# IMU_Raspberry_Pi_Breakout_RevB.net
KiCad netlist of a schematic drawn in EAGLE
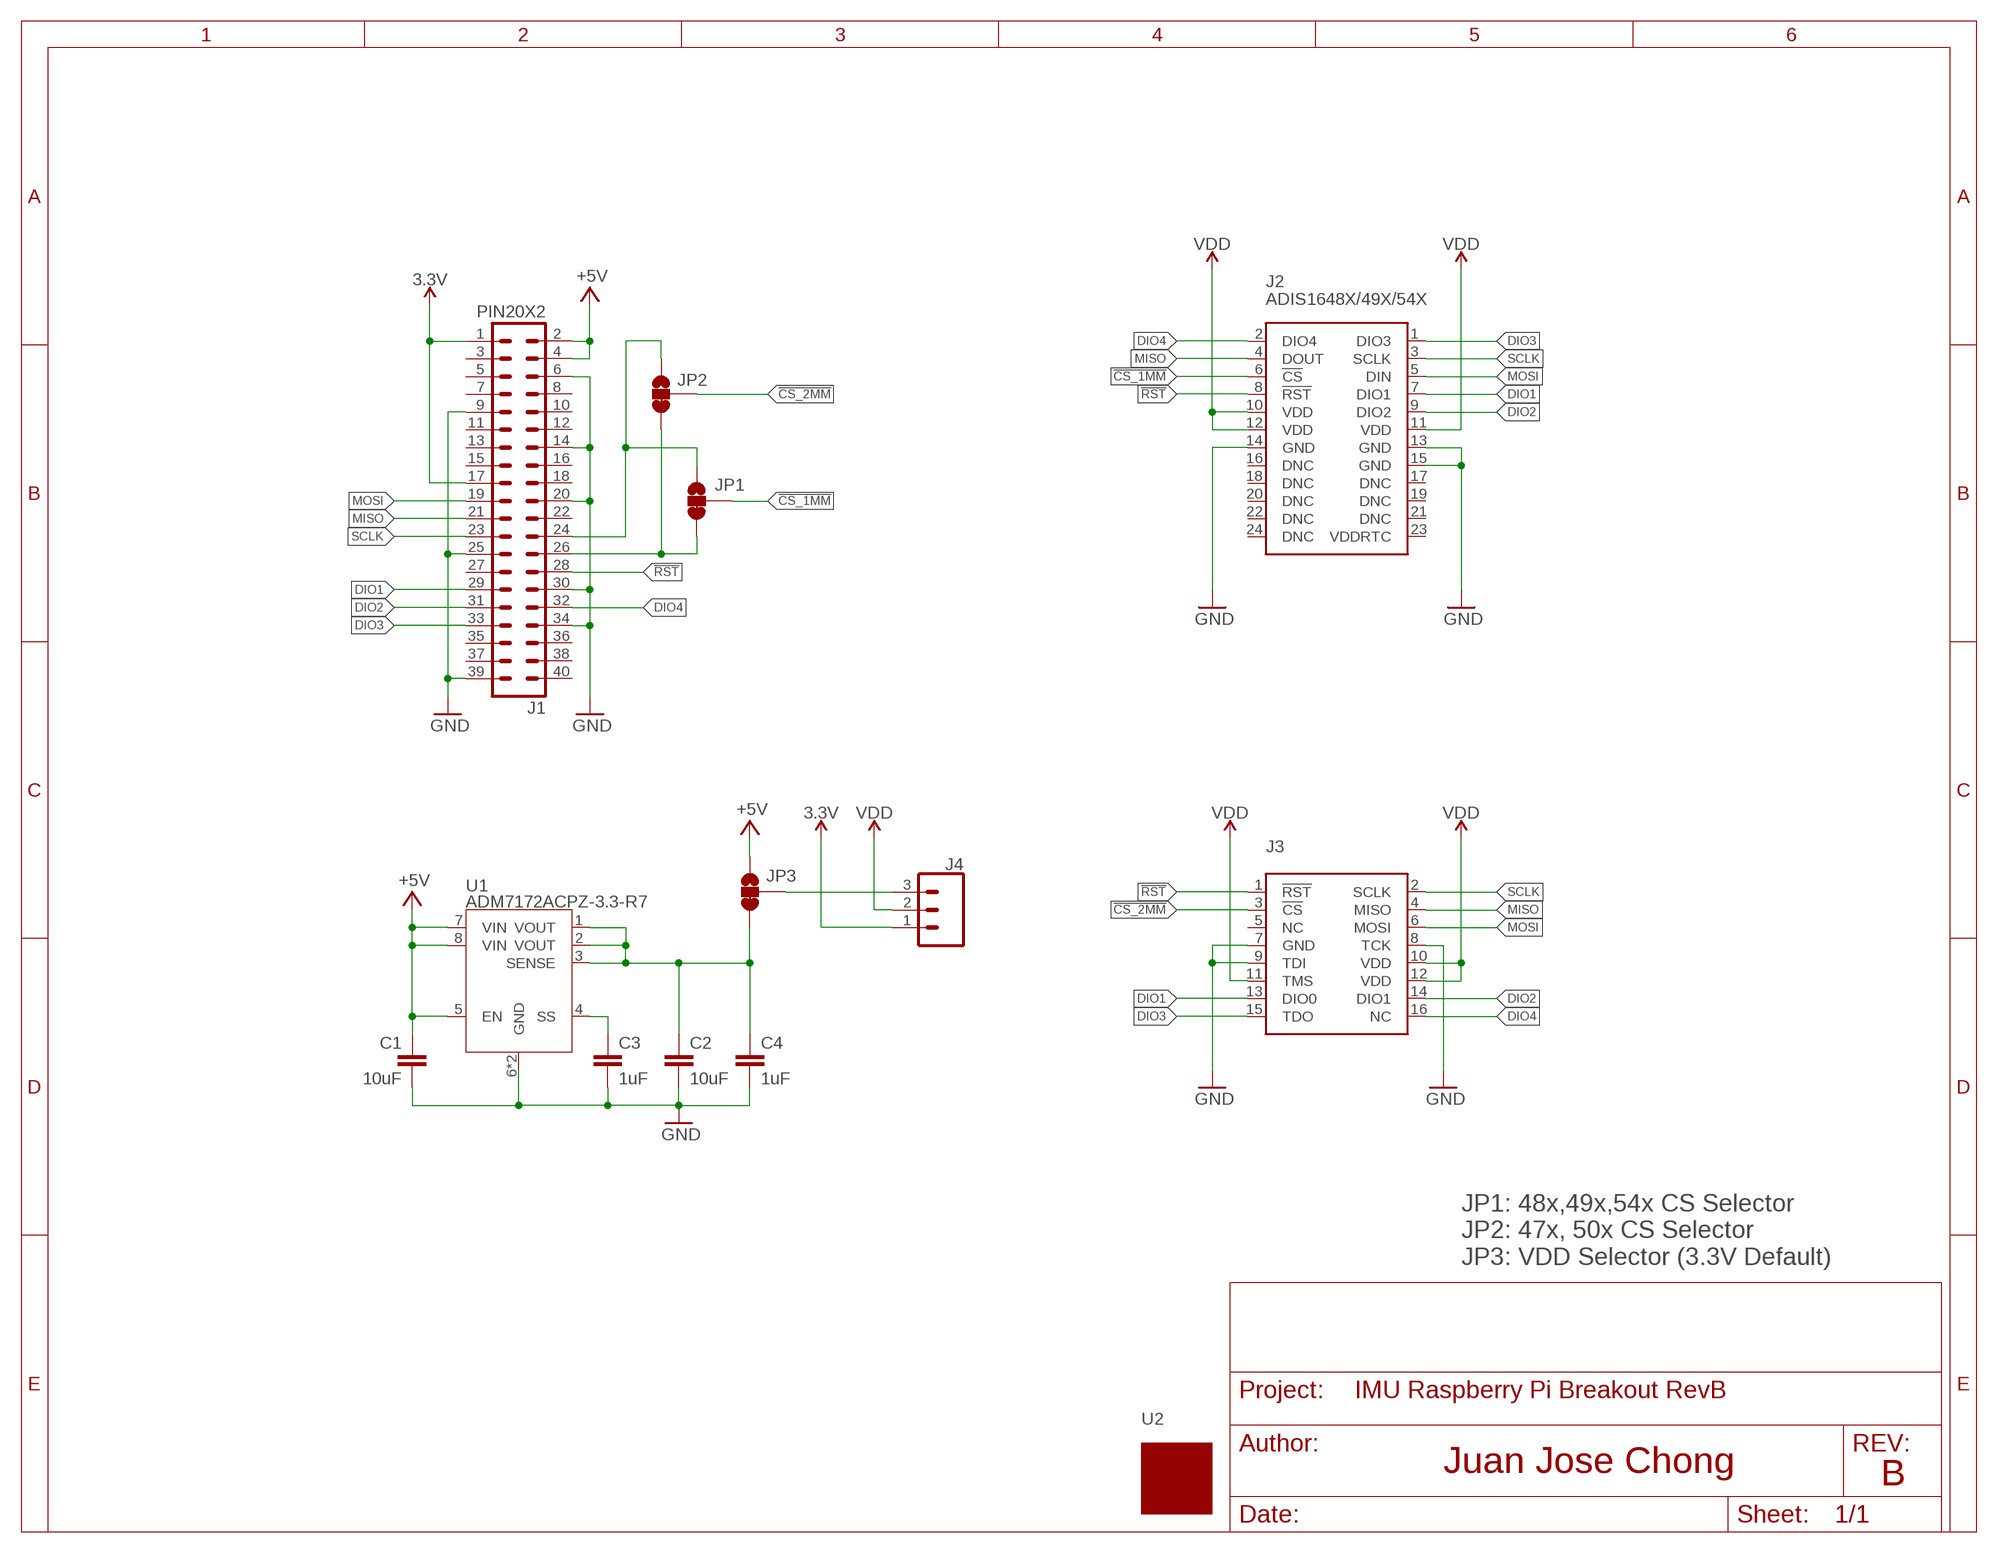
[diagram p0: schematic, sheet 1]

(export (version "E")
  (design (tool "Eeschema 10.0.6"))
  (components
    (comp (ref "C1")
      (value "10uF")
      (footprint "eagle-import:0805")
      (libsource (lib "eagle-import") (part "CAP-0805"))
    )
    (comp (ref "C2")
      (value "10uF")
      (footprint "eagle-import:0805")
      (libsource (lib "eagle-import") (part "CAP-0805"))
    )
    (comp (ref "C3")
      (value "1uF")
      (footprint "eagle-import:0603")
      (libsource (lib "eagle-import") (part "CAP-0603"))
    )
    (comp (ref "C4")
      (value "1uF")
      (footprint "eagle-import:0603")
      (libsource (lib "eagle-import") (part "CAP-0603"))
    )
    (comp (ref "J1")
      (value "PIN20X2")
      (footprint "eagle-import:PIN_20X2")
      (libsource (lib "eagle-import") (part "PIN20X2"))
    )
    (comp (ref "J2")
      (value "ADIS1648X/49X/54X")
      (footprint "eagle-import:ADIS1648X-TAPPED")
      (libsource (lib "eagle-import") (part "ADIS1648X/ADIS1649XTAPPED"))
    )
    (comp (ref "J3")
      (value "ADIS_EVAL_16PIN_2MM")
      (footprint "eagle-import:A3-16PA-2SV(71)-TOP")
      (libsource (lib "eagle-import") (part "ADIS_EVAL_16PIN_2MM"))
    )
    (comp (ref "J4")
      (value "455-1750-1-ND")
      (footprint "eagle-import:1X03")
      (libsource (lib "eagle-import") (part "CONN_03"))
    )
    (comp (ref "JP1")
      (value "JUMPER-SMT_3_1-NC_TRACE_SILK")
      (footprint "eagle-import:SMT-JUMPER_3_1-NC_TRACE_SILK")
      (libsource (lib "eagle-import") (part "JUMPER-SMT_3_1-NC_TRACE_SILK"))
    )
    (comp (ref "JP2")
      (value "JUMPER-SMT_3_1-NC_TRACE_SILK")
      (footprint "eagle-import:SMT-JUMPER_3_1-NC_TRACE_SILK")
      (libsource (lib "eagle-import") (part "JUMPER-SMT_3_1-NC_TRACE_SILK"))
    )
    (comp (ref "JP3")
      (value "JUMPER-SMT_3_1-NC_TRACE_SILK")
      (footprint "eagle-import:SMT-JUMPER_3_1-NC_TRACE_SILK")
      (libsource (lib "eagle-import") (part "JUMPER-SMT_3_1-NC_TRACE_SILK"))
    )
    (comp (ref "U1")
      (value "ADM7172ACPZ-3.3-R7")
      (footprint "eagle-import:LFCSP-8")
      (libsource (lib "eagle-import") (part "ADM7172ACPZ-3.3-R7"))
    )
    (comp (ref "U2")
      (value "ADIS16XXX_COUPON")
      (footprint "eagle-import:ADIS16XXX_COUPON")
      (libsource (lib "eagle-import") (part "ADIS16XXX_COUPON"))
    )
  )
  (nets
    (net (code "1") (name "+5V") (class "Default")
      (node (ref "C1") (pin "1") (pinfunction "1_1") (pintype "passive"))
      (node (ref "J1") (pin "2") (pinfunction "2_2") (pintype "passive"))
      (node (ref "J1") (pin "4") (pinfunction "4_4") (pintype "passive"))
      (node (ref "JP3") (pin "1") (pinfunction "1_1") (pintype "passive"))
      (node (ref "U1") (pin "5") (pinfunction "EN_5") (pintype "bidirectional"))
      (node (ref "U1") (pin "7") (pinfunction "VIN_7") (pintype "bidirectional"))
      (node (ref "U1") (pin "8") (pinfunction "VIN_8") (pintype "bidirectional"))
    )
    (net (code "2") (name "/~{CS_1MM}") (class "Default")
      (node (ref "J2") (pin "6") (pinfunction "~{CS}_6") (pintype "bidirectional"))
      (node (ref "JP1") (pin "2") (pinfunction "2_2") (pintype "passive"))
    )
    (net (code "3") (name "/~{CS_2MM}") (class "Default")
      (node (ref "J3") (pin "3") (pinfunction "~{CS}_3") (pintype "bidirectional"))
      (node (ref "JP2") (pin "2") (pinfunction "2_2") (pintype "passive"))
    )
    (net (code "4") (name "/~{RST}") (class "Default")
      (node (ref "J1") (pin "28") (pinfunction "28_28") (pintype "passive"))
      (node (ref "J2") (pin "8") (pinfunction "~{RST}_8") (pintype "bidirectional"))
      (node (ref "J3") (pin "1") (pinfunction "~{RST}_1") (pintype "bidirectional"))
    )
    (net (code "5") (name "3.3V") (class "Default")
      (node (ref "J1") (pin "1") (pinfunction "1_1") (pintype "passive"))
      (node (ref "J1") (pin "17") (pinfunction "17_17") (pintype "passive"))
      (node (ref "J4") (pin "1") (pinfunction "1_1") (pintype "passive"))
    )
    (net (code "6") (name "DIO1") (class "Default")
      (node (ref "J1") (pin "29") (pinfunction "29_29") (pintype "passive"))
      (node (ref "J2") (pin "7") (pinfunction "DIO1_7") (pintype "bidirectional"))
      (node (ref "J3") (pin "13") (pinfunction "DIO0_13") (pintype "bidirectional"))
    )
    (net (code "7") (name "DIO2") (class "Default")
      (node (ref "J1") (pin "31") (pinfunction "31_31") (pintype "passive"))
      (node (ref "J2") (pin "9") (pinfunction "DIO2_9") (pintype "bidirectional"))
      (node (ref "J3") (pin "14") (pinfunction "DIO1_14") (pintype "bidirectional"))
    )
    (net (code "8") (name "DIO3") (class "Default")
      (node (ref "J1") (pin "33") (pinfunction "33_33") (pintype "passive"))
      (node (ref "J2") (pin "1") (pinfunction "DIO3_1") (pintype "bidirectional"))
      (node (ref "J3") (pin "15") (pinfunction "TDO_15") (pintype "bidirectional"))
    )
    (net (code "9") (name "DIO4") (class "Default")
      (node (ref "J1") (pin "32") (pinfunction "32_32") (pintype "passive"))
      (node (ref "J2") (pin "2") (pinfunction "DIO4_2") (pintype "bidirectional"))
      (node (ref "J3") (pin "16") (pinfunction "NC_16") (pintype "bidirectional"))
    )
    (net (code "10") (name "GND") (class "Default")
      (node (ref "C1") (pin "2") (pinfunction "2_2") (pintype "passive"))
      (node (ref "C2") (pin "2") (pinfunction "2_2") (pintype "passive"))
      (node (ref "C3") (pin "2") (pinfunction "2_2") (pintype "passive"))
      (node (ref "C4") (pin "2") (pinfunction "2_2") (pintype "passive"))
      (node (ref "J1") (pin "14") (pinfunction "14_14") (pintype "passive"))
      (node (ref "J1") (pin "20") (pinfunction "20_20") (pintype "passive"))
      (node (ref "J1") (pin "25") (pinfunction "25_25") (pintype "passive"))
      (node (ref "J1") (pin "30") (pinfunction "30_30") (pintype "passive"))
      (node (ref "J1") (pin "34") (pinfunction "34_34") (pintype "passive"))
      (node (ref "J1") (pin "39") (pinfunction "39_39") (pintype "passive"))
      (node (ref "J1") (pin "6") (pinfunction "6_6") (pintype "passive"))
      (node (ref "J1") (pin "9") (pinfunction "9_9") (pintype "passive"))
      (node (ref "J2") (pin "13") (pinfunction "GND_13") (pintype "bidirectional"))
      (node (ref "J2") (pin "14") (pinfunction "GND_14") (pintype "bidirectional"))
      (node (ref "J2") (pin "15") (pinfunction "GND_15") (pintype "bidirectional"))
      (node (ref "J3") (pin "7") (pinfunction "GND_7") (pintype "bidirectional"))
      (node (ref "J3") (pin "8") (pinfunction "TCK_8") (pintype "bidirectional"))
      (node (ref "J3") (pin "9") (pinfunction "TDI_9") (pintype "bidirectional"))
      (node (ref "U1") (pin "6") (pinfunction "GND_6") (pintype "bidirectional"))
      (node (ref "U1") (pin "9") (pinfunction "GND_9") (pintype "bidirectional"))
    )
    (net (code "11") (name "MISO") (class "Default")
      (node (ref "J1") (pin "21") (pinfunction "21_21") (pintype "passive"))
      (node (ref "J2") (pin "4") (pinfunction "DOUT_4") (pintype "bidirectional"))
      (node (ref "J3") (pin "4") (pinfunction "MISO_4") (pintype "bidirectional"))
    )
    (net (code "12") (name "MOSI") (class "Default")
      (node (ref "J1") (pin "19") (pinfunction "19_19") (pintype "passive"))
      (node (ref "J2") (pin "5") (pinfunction "DIN_5") (pintype "bidirectional"))
      (node (ref "J3") (pin "6") (pinfunction "MOSI_6") (pintype "bidirectional"))
    )
    (net (code "13") (name "Net-(J1-Pad24)") (class "Default")
      (node (ref "J1") (pin "24") (pinfunction "24_24") (pintype "passive"))
      (node (ref "JP1") (pin "1") (pinfunction "1_1") (pintype "passive"))
      (node (ref "JP2") (pin "1") (pinfunction "1_1") (pintype "passive"))
    )
    (net (code "14") (name "Net-(J1-Pad26)") (class "Default")
      (node (ref "J1") (pin "26") (pinfunction "26_26") (pintype "passive"))
      (node (ref "JP1") (pin "3") (pinfunction "3_3") (pintype "passive"))
      (node (ref "JP2") (pin "3") (pinfunction "3_3") (pintype "passive"))
    )
    (net (code "15") (name "Net-(J4-Pad3)") (class "Default")
      (node (ref "J4") (pin "3") (pinfunction "3_3") (pintype "passive"))
      (node (ref "JP3") (pin "2") (pinfunction "2_2") (pintype "passive"))
    )
    (net (code "16") (name "Net-(U1-SENSE)") (class "Default")
      (node (ref "C2") (pin "1") (pinfunction "1_1") (pintype "passive"))
      (node (ref "C4") (pin "1") (pinfunction "1_1") (pintype "passive"))
      (node (ref "JP3") (pin "3") (pinfunction "3_3") (pintype "passive"))
      (node (ref "U1") (pin "1") (pinfunction "VOUT_1") (pintype "bidirectional"))
      (node (ref "U1") (pin "2") (pinfunction "VOUT_2") (pintype "bidirectional"))
      (node (ref "U1") (pin "3") (pinfunction "SENSE_3") (pintype "bidirectional"))
    )
    (net (code "17") (name "Net-(U1-SS)") (class "Default")
      (node (ref "C3") (pin "1") (pinfunction "1_1") (pintype "passive"))
      (node (ref "U1") (pin "4") (pinfunction "SS_4") (pintype "bidirectional"))
    )
    (net (code "18") (name "SCLK") (class "Default")
      (node (ref "J1") (pin "23") (pinfunction "23_23") (pintype "passive"))
      (node (ref "J2") (pin "3") (pinfunction "SCLK_3") (pintype "bidirectional"))
      (node (ref "J3") (pin "2") (pinfunction "SCLK_2") (pintype "bidirectional"))
    )
    (net (code "19") (name "VDD") (class "Default")
      (node (ref "J2") (pin "10") (pinfunction "VDD_10") (pintype "bidirectional"))
      (node (ref "J2") (pin "11") (pinfunction "VDD_11") (pintype "bidirectional"))
      (node (ref "J2") (pin "12") (pinfunction "VDD_12") (pintype "bidirectional"))
      (node (ref "J3") (pin "10") (pinfunction "VDD_10") (pintype "bidirectional"))
      (node (ref "J3") (pin "11") (pinfunction "TMS_11") (pintype "bidirectional"))
      (node (ref "J3") (pin "12") (pinfunction "VDD_12") (pintype "bidirectional"))
      (node (ref "J4") (pin "2") (pinfunction "2_2") (pintype "passive"))
    )
    (net (code "20") (name "unconnected-(J1-Pad3)") (class "Default")
      (node (ref "J1") (pin "3") (pinfunction "3_3") (pintype "passive"))
    )
    (net (code "21") (name "unconnected-(J1-Pad5)") (class "Default")
      (node (ref "J1") (pin "5") (pinfunction "5_5") (pintype "passive"))
    )
    (net (code "22") (name "unconnected-(J1-Pad7)") (class "Default")
      (node (ref "J1") (pin "7") (pinfunction "7_7") (pintype "passive"))
    )
    (net (code "23") (name "unconnected-(J1-Pad8)") (class "Default")
      (node (ref "J1") (pin "8") (pinfunction "8_8") (pintype "passive"))
    )
    (net (code "24") (name "unconnected-(J1-Pad10)") (class "Default")
      (node (ref "J1") (pin "10") (pinfunction "10_10") (pintype "passive"))
    )
    (net (code "25") (name "unconnected-(J1-Pad11)") (class "Default")
      (node (ref "J1") (pin "11") (pinfunction "11_11") (pintype "passive"))
    )
    (net (code "26") (name "unconnected-(J1-Pad12)") (class "Default")
      (node (ref "J1") (pin "12") (pinfunction "12_12") (pintype "passive"))
    )
    (net (code "27") (name "unconnected-(J1-Pad13)") (class "Default")
      (node (ref "J1") (pin "13") (pinfunction "13_13") (pintype "passive"))
    )
    (net (code "28") (name "unconnected-(J1-Pad15)") (class "Default")
      (node (ref "J1") (pin "15") (pinfunction "15_15") (pintype "passive"))
    )
    (net (code "29") (name "unconnected-(J1-Pad16)") (class "Default")
      (node (ref "J1") (pin "16") (pinfunction "16_16") (pintype "passive"))
    )
    (net (code "30") (name "unconnected-(J1-Pad18)") (class "Default")
      (node (ref "J1") (pin "18") (pinfunction "18_18") (pintype "passive"))
    )
    (net (code "31") (name "unconnected-(J1-Pad22)") (class "Default")
      (node (ref "J1") (pin "22") (pinfunction "22_22") (pintype "passive"))
    )
    (net (code "32") (name "unconnected-(J1-Pad27)") (class "Default")
      (node (ref "J1") (pin "27") (pinfunction "27_27") (pintype "passive"))
    )
    (net (code "33") (name "unconnected-(J1-Pad35)") (class "Default")
      (node (ref "J1") (pin "35") (pinfunction "35_35") (pintype "passive"))
    )
    (net (code "34") (name "unconnected-(J1-Pad36)") (class "Default")
      (node (ref "J1") (pin "36") (pinfunction "36_36") (pintype "passive"))
    )
    (net (code "35") (name "unconnected-(J1-Pad37)") (class "Default")
      (node (ref "J1") (pin "37") (pinfunction "37_37") (pintype "passive"))
    )
    (net (code "36") (name "unconnected-(J1-Pad38)") (class "Default")
      (node (ref "J1") (pin "38") (pinfunction "38_38") (pintype "passive"))
    )
    (net (code "37") (name "unconnected-(J1-Pad40)") (class "Default")
      (node (ref "J1") (pin "40") (pinfunction "40_40") (pintype "passive"))
    )
    (net (code "38") (name "unconnected-(J2-DNC-Pad16)") (class "Default")
      (node (ref "J2") (pin "16") (pinfunction "DNC_16") (pintype "bidirectional"))
    )
    (net (code "39") (name "unconnected-(J2-DNC-Pad17)") (class "Default")
      (node (ref "J2") (pin "17") (pinfunction "DNC_17") (pintype "bidirectional"))
    )
    (net (code "40") (name "unconnected-(J2-DNC-Pad18)") (class "Default")
      (node (ref "J2") (pin "18") (pinfunction "DNC_18") (pintype "bidirectional"))
    )
    (net (code "41") (name "unconnected-(J2-DNC-Pad19)") (class "Default")
      (node (ref "J2") (pin "19") (pinfunction "DNC_19") (pintype "bidirectional"))
    )
    (net (code "42") (name "unconnected-(J2-DNC-Pad20)") (class "Default")
      (node (ref "J2") (pin "20") (pinfunction "DNC_20") (pintype "bidirectional"))
    )
    (net (code "43") (name "unconnected-(J2-DNC-Pad21)") (class "Default")
      (node (ref "J2") (pin "21") (pinfunction "DNC_21") (pintype "bidirectional"))
    )
    (net (code "44") (name "unconnected-(J2-DNC-Pad22)") (class "Default")
      (node (ref "J2") (pin "22") (pinfunction "DNC_22") (pintype "bidirectional"))
    )
    (net (code "45") (name "unconnected-(J2-DNC-Pad24)") (class "Default")
      (node (ref "J2") (pin "24") (pinfunction "DNC_24") (pintype "bidirectional"))
    )
    (net (code "46") (name "unconnected-(J2-VDDRTC-Pad23)") (class "Default")
      (node (ref "J2") (pin "23") (pinfunction "VDDRTC_23") (pintype "bidirectional"))
    )
    (net (code "47") (name "unconnected-(J3-NC-Pad5)") (class "Default")
      (node (ref "J3") (pin "5") (pinfunction "NC_5") (pintype "bidirectional"))
    )
  )
)
